# openSX70_ALADDIN_V399SEEED_20180220.net
KiCad netlist of a schematic drawn in EAGLE
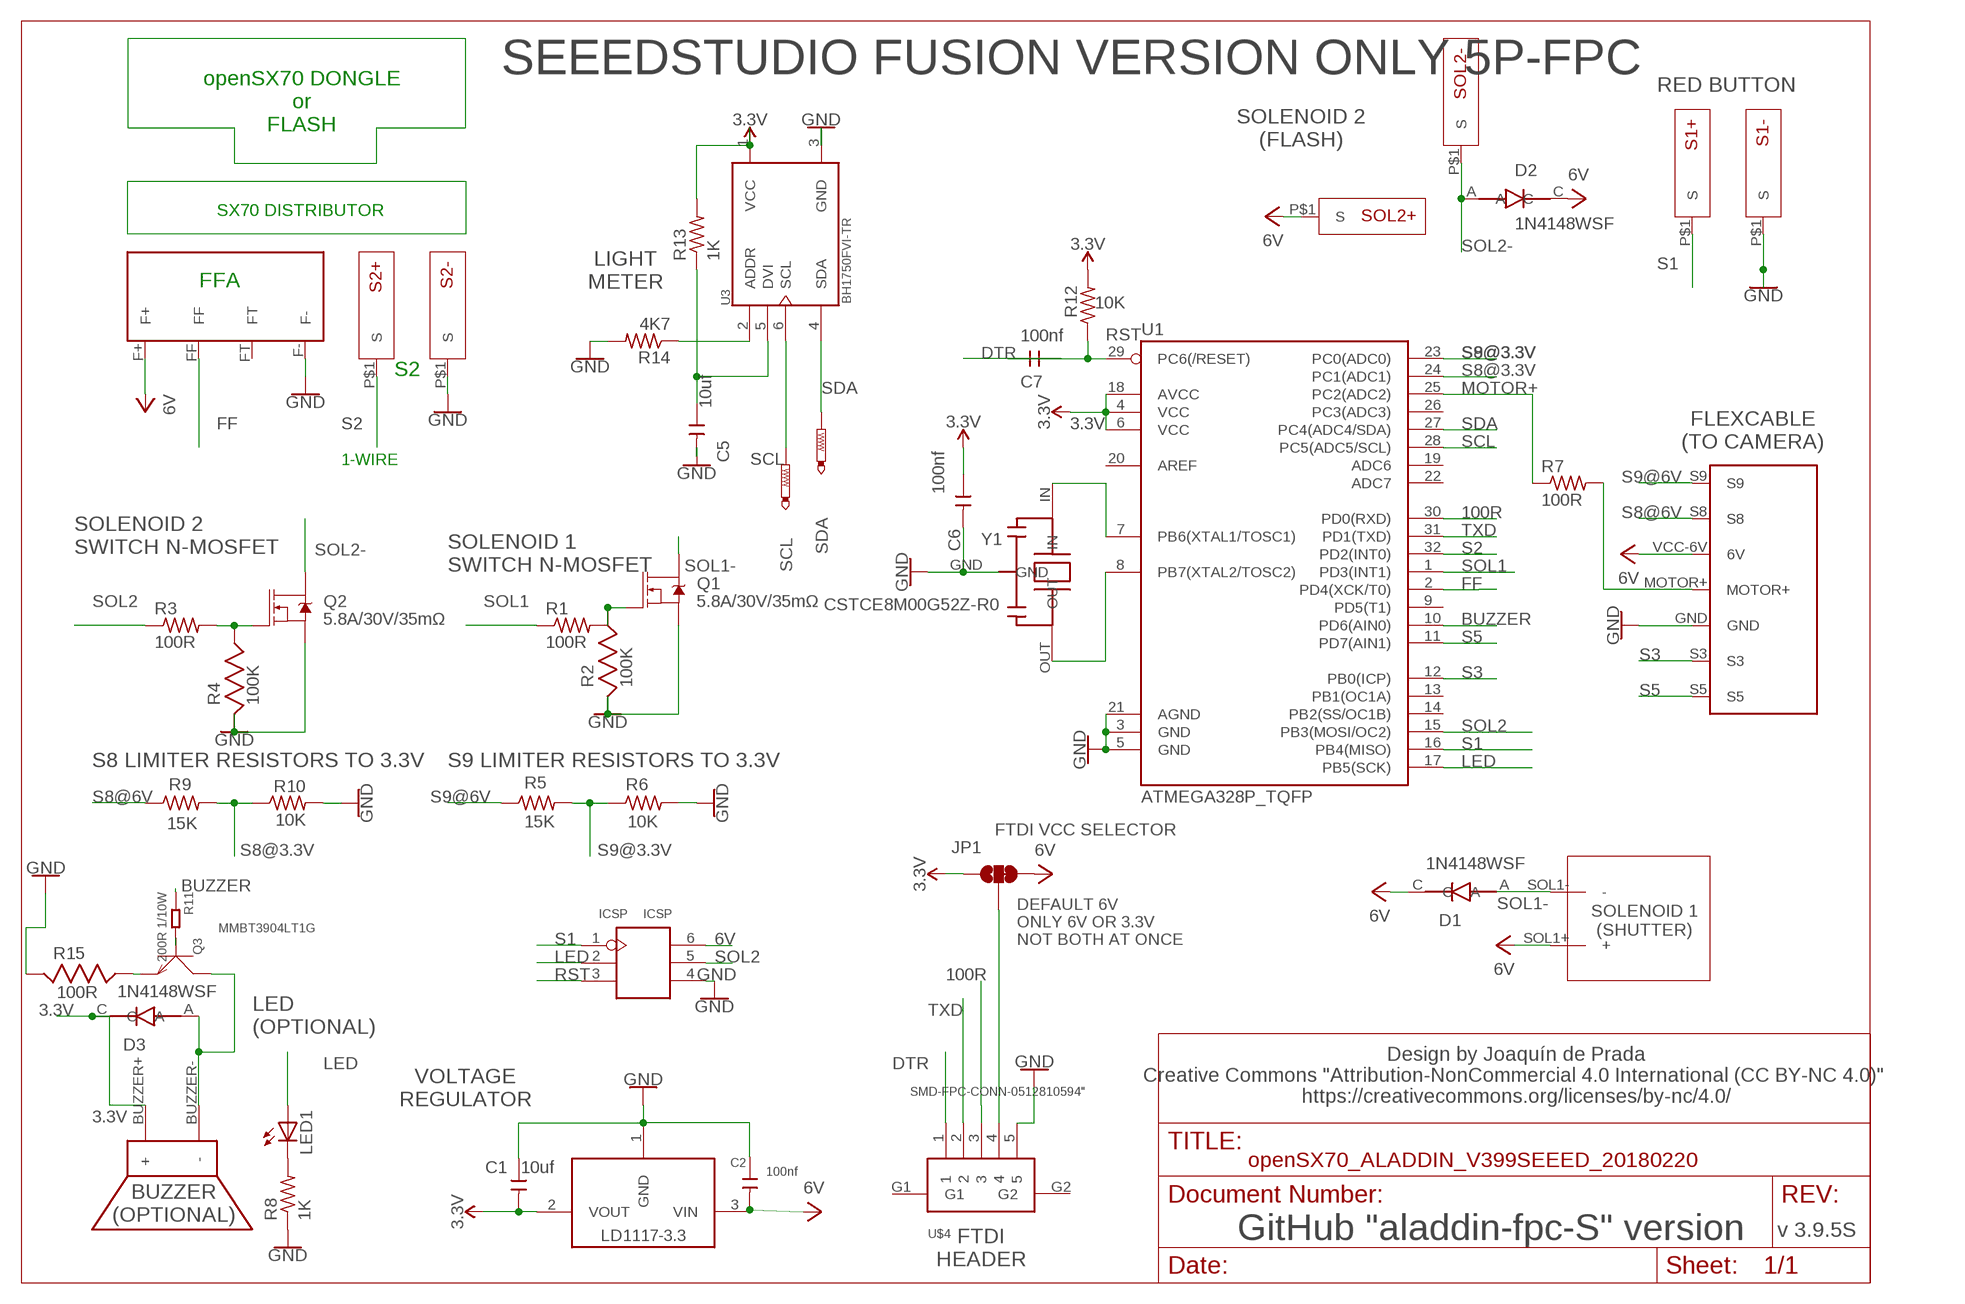
[diagram p0: schematic, sheet 1]

(export (version "E")
  (design (tool "Eeschema 10.0.6"))
  (components
    (comp (ref "C1")
      (value "10uf")
      (footprint "eagle-import:C0603")
      (fields (field (name "MPN") "CC0603KRX5R6BB106"))
      (libsource (lib "eagle-import") (part "CERAMIC-10UF-10V-10%-X5R(0603)"))
    )
    (comp (ref "C2")
      (value "100nf")
      (footprint "eagle-import:C0603")
      (fields (field (name "MPN") "CC0603KRX7R9BB104"))
      (libsource (lib "eagle-import") (part "CERAMIC-100NF-50V-10%-X7R(0603)"))
    )
    (comp (ref "C5")
      (value "10uf")
      (footprint "eagle-import:C0603")
      (fields (field (name "MPN") "CC0603KRX5R6BB106"))
      (libsource (lib "eagle-import") (part "CERAMIC-10UF-10V-10%-X5R(0603)"))
    )
    (comp (ref "C6")
      (value "100nf")
      (footprint "eagle-import:C0603")
      (fields (field (name "MPN") "CC0603KRX7R9BB104"))
      (libsource (lib "eagle-import") (part "CERAMIC-100NF-50V-10%-X7R(0603)"))
    )
    (comp (ref "C7")
      (value "100nf")
      (footprint "eagle-import:C0603")
      (fields (field (name "MPN") "CC0603KRX7R9BB104"))
      (libsource (lib "eagle-import") (part "CERAMIC-100NF-50V-10%-X7R(0603)"))
    )
    (comp (ref "D1")
      (value "1N4148WSF")
      (footprint "eagle-import:SODFL2512X100N")
      (fields (field (name "MANUFACTURER") "Fairchild Semiconductor"))
      (libsource (lib "eagle-import") (part "1N4148WS"))
    )
    (comp (ref "D2")
      (value "1N4148WSF")
      (footprint "eagle-import:SODFL2512X100N")
      (fields (field (name "MANUFACTURER") "Fairchild Semiconductor"))
      (libsource (lib "eagle-import") (part "1N4148WS"))
    )
    (comp (ref "D3")
      (value "1N4148WSF")
      (footprint "eagle-import:SODFL2512X100N")
      (fields (field (name "MANUFACTURER") "Fairchild Semiconductor"))
      (libsource (lib "eagle-import") (part "1N4148WS"))
    )
    (comp (ref "ICSP")
      (value "ICSP")
      (footprint "eagle-import:H2X3-2.54")
      (libsource (lib "eagle-import") (part "ICSP"))
    )
    (comp (ref "JP1")
      (value "FTDI VCC SELECTOR")
      (footprint "eagle-import:SMT-JUMPER_3_1-NC_TRACE_SILK")
      (libsource (lib "eagle-import") (part "JUMPER-SMT_3_1-NC_TRACE_SILK"))
    )
    (comp (ref "LD11172.5V")
      (value "LD1117 2.5V")
      (footprint "eagle-import:SOT223")
      (fields (field (name "MF") "Advanced Monolithic Systems") (field (name "MP") "AMS1117-5.0"))
      (libsource (lib "eagle-import") (part "LD1117-3.3"))
    )
    (comp (ref "LED1")
      (value "LEDCHIPLED_0805")
      (footprint "eagle-import:CHIPLED_0805")
      (libsource (lib "eagle-import") (part "LEDCHIPLED_0805"))
    )
    (comp (ref "Q1")
      (value "5.8A/30V/35mΩ")
      (footprint "eagle-import:SOT23-3")
      (libsource (lib "eagle-import") (part "MOSFET-NCH-AO3404A"))
    )
    (comp (ref "Q2")
      (value "5.8A/30V/35mΩ")
      (footprint "eagle-import:SOT23-3")
      (libsource (lib "eagle-import") (part "MOSFET-NCH-AO3404A"))
    )
    (comp (ref "Q3")
      (value "MMBT3904LT1G")
      (footprint "eagle-import:SOT-23")
      (libsource (lib "eagle-import") (part "SMD-TRANSISTORS-NPN-40V-200MA-MMBT3904LT1G(SOT-23)"))
    )
    (comp (ref "R1")
      (value "100R")
      (footprint "eagle-import:R0603")
      (libsource (lib "eagle-import") (part "R-US_R0603"))
    )
    (comp (ref "R2")
      (value "100K")
      (footprint "eagle-import:ERJ-3EKF1003V_RESC1608X55")
      (fields (field (name "MANUFACTURER") "PANASONIC"))
      (libsource (lib "eagle-import") (part "ERJ-3EKF1003V"))
    )
    (comp (ref "R3")
      (value "100R")
      (footprint "eagle-import:R0603")
      (libsource (lib "eagle-import") (part "R-US_R0603"))
    )
    (comp (ref "R4")
      (value "100K")
      (footprint "eagle-import:ERJ-3EKF1003V_RESC1608X55")
      (fields (field (name "MANUFACTURER") "PANASONIC"))
      (libsource (lib "eagle-import") (part "ERJ-3EKF1003V"))
    )
    (comp (ref "R5")
      (value "15K")
      (footprint "eagle-import:R0603")
      (libsource (lib "eagle-import") (part "R-US_R0603"))
    )
    (comp (ref "R6")
      (value "10K")
      (footprint "eagle-import:R0603")
      (libsource (lib "eagle-import") (part "R-US_R0603"))
    )
    (comp (ref "R7")
      (value "100R")
      (footprint "eagle-import:R0603")
      (libsource (lib "eagle-import") (part "R-US_R0603"))
    )
    (comp (ref "R8")
      (value "1K")
      (footprint "eagle-import:R0603")
      (libsource (lib "eagle-import") (part "R-US_R0603"))
    )
    (comp (ref "R9")
      (value "15K")
      (footprint "eagle-import:R0603")
      (libsource (lib "eagle-import") (part "R-US_R0603"))
    )
    (comp (ref "R10")
      (value "10K")
      (footprint "eagle-import:R0603")
      (libsource (lib "eagle-import") (part "R-US_R0603"))
    )
    (comp (ref "R11")
      (value "200R 1/10W")
      (footprint "eagle-import:R0603")
      (fields (field (name "MPN") "RC0603JR-07200RL"))
      (libsource (lib "eagle-import") (part "SMD-RES-200R-5%-1/10W(0603)"))
    )
    (comp (ref "R12")
      (value "10K")
      (footprint "eagle-import:R0603")
      (libsource (lib "eagle-import") (part "R-US_R0603"))
    )
    (comp (ref "R13")
      (value "1K")
      (footprint "eagle-import:R0603")
      (libsource (lib "eagle-import") (part "R-US_R0603"))
    )
    (comp (ref "R14")
      (value "4K7")
      (footprint "eagle-import:R0603")
      (libsource (lib "eagle-import") (part "R-US_R0603"))
    )
    (comp (ref "R15")
      (value "CRCW0603100RFKEA")
      (footprint "eagle-import:CRCW0603100RFKEA_RESC1608X55")
      (fields (field (name "MANUFACTURER") "VISHAY"))
      (libsource (lib "eagle-import") (part "CRCW0603100RFKEA"))
    )
    (comp (ref "S1+")
      (value "SX70-S-PAD-NEW")
      (footprint "eagle-import:SX70-S-PAD2")
      (libsource (lib "eagle-import") (part "SX70-S-PAD-NEW"))
    )
    (comp (ref "S1-")
      (value "SX70-S-PAD-NEW")
      (footprint "eagle-import:SX70-S-PAD2")
      (libsource (lib "eagle-import") (part "SX70-S-PAD-NEW"))
    )
    (comp (ref "S2+")
      (value "SX70-S-PAD-NEW")
      (footprint "eagle-import:SX70-S-PAD2")
      (libsource (lib "eagle-import") (part "SX70-S-PAD-NEW"))
    )
    (comp (ref "S2-")
      (value "SX70-S-PAD-NEW")
      (footprint "eagle-import:SX70-S-PAD2")
      (libsource (lib "eagle-import") (part "SX70-S-PAD-NEW"))
    )
    (comp (ref "SCL")
      (value "PTR1TP08R")
      (footprint "eagle-import:TP08R")
      (libsource (lib "eagle-import") (part "PTR1TP08R"))
    )
    (comp (ref "SDA")
      (value "PTR1TP08R")
      (footprint "eagle-import:TP08R")
      (libsource (lib "eagle-import") (part "PTR1TP08R"))
    )
    (comp (ref "SOL1")
      (value "SX70-SOLENOID1-2PADS")
      (footprint "eagle-import:SX70-SOLENOID1-2")
      (libsource (lib "eagle-import") (part "SX70-SOLENOID1-2PADS"))
    )
    (comp (ref "SOL2+")
      (value "SX70-S-PAD-NEW")
      (footprint "eagle-import:SX70-S-PAD2")
      (libsource (lib "eagle-import") (part "SX70-S-PAD-NEW"))
    )
    (comp (ref "SOL2-")
      (value "SX70-S-PAD-NEW")
      (footprint "eagle-import:SX70-S-PAD2")
      (libsource (lib "eagle-import") (part "SX70-S-PAD-NEW"))
    )
    (comp (ref "U$1")
      (value "SX70-7-PAD")
      (footprint "eagle-import:SX70-7-PAD")
      (libsource (lib "eagle-import") (part "SX70-7-PAD"))
    )
    (comp (ref "U$2")
      (value "FFA")
      (footprint "eagle-import:FFA-PAD-PACKAGE")
      (libsource (lib "eagle-import") (part "SX70-FFA-PAD"))
    )
    (comp (ref "U$3")
      (value "CSET8-5G_V2")
      (footprint "eagle-import:CSET8-5G_PACKAGE")
      (libsource (lib "eagle-import") (part "CSET8-5G_V2"))
    )
    (comp (ref "U$4")
      (value "SMD-FPC-CONN-0512810594\"")
      (footprint "eagle-import:51281-0594")
      (libsource (lib "eagle-import") (part "SMD-FPC-CONN-0512810594{dblquote}"))
    )
    (comp (ref "U1")
      (value "ATMEGA328P_TQFP")
      (footprint "eagle-import:TQFP32-08")
      (libsource (lib "eagle-import") (part "ATMEGA328P_TQFP"))
    )
    (comp (ref "U3")
      (value "BH1750FVI-TR")
      (footprint "eagle-import:SOTFL50P300X75-6N")
      (fields (field (name "MF") "Rohm"))
      (libsource (lib "eagle-import") (part "BH1750FVI-TR"))
    )
    (comp (ref "Y1")
      (value "CSTCE8M00G52Z-R0")
      (footprint "eagle-import:CFP95P160X100-3N")
      (fields (field (name "MF") "Murata") (field (name "MP") "CSTCE16M0V53-R0"))
      (libsource (lib "eagle-import") (part "CSTCE16M0V53-R0"))
    )
  )
  (nets
    (net (code "1") (name "/100R") (class "Default")
      (node (ref "U$4") (pin "3") (pinfunction "3_3") (pintype "bidirectional"))
      (node (ref "U1") (pin "30") (pinfunction "PD0(RXD)_30") (pintype "bidirectional"))
    )
    (net (code "2") (name "/BUZZER") (class "Default")
      (node (ref "R11") (pin "1") (pinfunction "1_1") (pintype "passive"))
      (node (ref "U1") (pin "10") (pinfunction "PD6(AIN0)_10") (pintype "bidirectional"))
    )
    (net (code "3") (name "/DTR") (class "Default")
      (node (ref "C7") (pin "1") (pinfunction "1_1") (pintype "passive"))
      (node (ref "U$4") (pin "1") (pinfunction "1_1") (pintype "bidirectional"))
    )
    (net (code "4") (name "/FF") (class "Default")
      (node (ref "U$2") (pin "FF") (pinfunction "FF_FF") (pintype "bidirectional"))
      (node (ref "U1") (pin "2") (pinfunction "PD4(XCK/T0)_2") (pintype "bidirectional"))
    )
    (net (code "5") (name "/LED") (class "Default")
      (node (ref "ICSP") (pin "2") (pinfunction "SCK_2") (pintype "bidirectional"))
      (node (ref "LED1") (pin "A") (pinfunction "A_A") (pintype "passive"))
      (node (ref "U1") (pin "17") (pinfunction "PB5(SCK)_17") (pintype "bidirectional"))
    )
    (net (code "6") (name "/MOTOR+") (class "Default")
      (node (ref "R7") (pin "1") (pinfunction "1_1") (pintype "passive"))
      (node (ref "U1") (pin "25") (pinfunction "PC2(ADC2)_25") (pintype "bidirectional"))
    )
    (net (code "7") (name "/RST") (class "Default")
      (node (ref "C7") (pin "2") (pinfunction "2_2") (pintype "passive"))
      (node (ref "ICSP") (pin "3") (pinfunction "RST_3") (pintype "bidirectional"))
      (node (ref "R12") (pin "1") (pinfunction "1_1") (pintype "passive"))
      (node (ref "U1") (pin "29") (pinfunction "PC6(/RESET)_29") (pintype "bidirectional"))
    )
    (net (code "8") (name "/S1") (class "Default")
      (node (ref "ICSP") (pin "1") (pinfunction "MISO_1") (pintype "bidirectional"))
      (node (ref "S1+") (pin "P$1") (pinfunction "S_P$1") (pintype "bidirectional"))
      (node (ref "U1") (pin "16") (pinfunction "PB4(MISO)_16") (pintype "bidirectional"))
    )
    (net (code "9") (name "/S2") (class "Default")
      (node (ref "S2+") (pin "P$1") (pinfunction "S_P$1") (pintype "bidirectional"))
      (node (ref "U1") (pin "32") (pinfunction "PD2(INT0)_32") (pintype "bidirectional"))
    )
    (net (code "10") (name "/S3") (class "Default")
      (node (ref "U$1") (pin "S3") (pinfunction "S3_S3") (pintype "bidirectional"))
      (node (ref "U1") (pin "12") (pinfunction "PB0(ICP)_12") (pintype "bidirectional"))
    )
    (net (code "11") (name "/S5") (class "Default")
      (node (ref "U$1") (pin "S5") (pinfunction "S5_S5") (pintype "bidirectional"))
      (node (ref "U1") (pin "11") (pinfunction "PD7(AIN1)_11") (pintype "bidirectional"))
    )
    (net (code "12") (name "/S8@3.3V") (class "Default")
      (node (ref "R10") (pin "1") (pinfunction "1_1") (pintype "passive"))
      (node (ref "R9") (pin "2") (pinfunction "2_2") (pintype "passive"))
      (node (ref "U1") (pin "24") (pinfunction "PC1(ADC1)_24") (pintype "bidirectional"))
    )
    (net (code "13") (name "/S8@6V") (class "Default")
      (node (ref "R9") (pin "1") (pinfunction "1_1") (pintype "passive"))
      (node (ref "U$1") (pin "S8") (pinfunction "S8_S8") (pintype "bidirectional"))
    )
    (net (code "14") (name "/S9@3.3V") (class "Default")
      (node (ref "R5") (pin "2") (pinfunction "2_2") (pintype "passive"))
      (node (ref "R6") (pin "1") (pinfunction "1_1") (pintype "passive"))
      (node (ref "U1") (pin "23") (pinfunction "PC0(ADC0)_23") (pintype "bidirectional"))
    )
    (net (code "15") (name "/S9@6V") (class "Default")
      (node (ref "R5") (pin "1") (pinfunction "1_1") (pintype "passive"))
      (node (ref "U$1") (pin "S9") (pinfunction "S9_S9") (pintype "bidirectional"))
    )
    (net (code "16") (name "/SCL") (class "Default")
      (node (ref "SCL") (pin "TP") (pinfunction "TP_TP") (pintype "input"))
      (node (ref "U1") (pin "28") (pinfunction "PC5(ADC5/SCL)_28") (pintype "bidirectional"))
      (node (ref "U3") (pin "6") (pinfunction "SCL_6") (pintype "input"))
    )
    (net (code "17") (name "/SDA") (class "Default")
      (node (ref "SDA") (pin "TP") (pinfunction "TP_TP") (pintype "input"))
      (node (ref "U1") (pin "27") (pinfunction "PC4(ADC4/SDA)_27") (pintype "bidirectional"))
      (node (ref "U3") (pin "4") (pinfunction "SDA_4") (pintype "bidirectional"))
    )
    (net (code "18") (name "/SOL1") (class "Default")
      (node (ref "R1") (pin "1") (pinfunction "1_1") (pintype "passive"))
      (node (ref "U1") (pin "1") (pinfunction "PD3(INT1)_1") (pintype "bidirectional"))
    )
    (net (code "19") (name "/SOL1-") (class "Default")
      (node (ref "D1") (pin "A") (pinfunction "A_A") (pintype "passive"))
      (node (ref "Q1") (pin "3") (pinfunction "D_3") (pintype "bidirectional"))
      (node (ref "SOL1") (pin "SOL1-") (pinfunction "-_SOL1-") (pintype "bidirectional"))
    )
    (net (code "20") (name "/SOL2") (class "Default")
      (node (ref "ICSP") (pin "5") (pinfunction "MOSI_5") (pintype "bidirectional"))
      (node (ref "R3") (pin "1") (pinfunction "1_1") (pintype "passive"))
      (node (ref "U1") (pin "15") (pinfunction "PB3(MOSI/OC2)_15") (pintype "bidirectional"))
    )
    (net (code "21") (name "/SOL2-") (class "Default")
      (node (ref "D2") (pin "A") (pinfunction "A_A") (pintype "passive"))
      (node (ref "Q2") (pin "3") (pinfunction "D_3") (pintype "bidirectional"))
      (node (ref "SOL2-") (pin "P$1") (pinfunction "S_P$1") (pintype "bidirectional"))
    )
    (net (code "22") (name "/TXD") (class "Default")
      (node (ref "U$4") (pin "2") (pinfunction "2_2") (pintype "bidirectional"))
      (node (ref "U1") (pin "31") (pinfunction "PD1(TXD)_31") (pintype "bidirectional"))
    )
    (net (code "23") (name "3.3V") (class "Default")
      (node (ref "C1") (pin "2") (pinfunction "2_2") (pintype "passive"))
      (node (ref "C6") (pin "1") (pinfunction "1_1") (pintype "passive"))
      (node (ref "D3") (pin "C") (pinfunction "C_C") (pintype "passive"))
      (node (ref "JP1") (pin "1") (pinfunction "1_1") (pintype "passive"))
      (node (ref "LD11172.5V") (pin "2") (pinfunction "VOUT_2") (pintype "bidirectional"))
      (node (ref "R12") (pin "2") (pinfunction "2_2") (pintype "passive"))
      (node (ref "R13") (pin "2") (pinfunction "2_2") (pintype "passive"))
      (node (ref "U$3") (pin "BUZZER+") (pinfunction "+_BUZZER+") (pintype "bidirectional"))
      (node (ref "U1") (pin "18") (pinfunction "AVCC_18") (pintype "bidirectional"))
      (node (ref "U1") (pin "4") (pinfunction "VCC_4") (pintype "bidirectional"))
      (node (ref "U1") (pin "6") (pinfunction "VCC_6") (pintype "bidirectional"))
      (node (ref "U3") (pin "1") (pinfunction "VCC_1") (pintype "power_in"))
    )
    (net (code "24") (name "6V") (class "Default")
      (node (ref "C2") (pin "2") (pinfunction "2_2") (pintype "passive"))
      (node (ref "D1") (pin "C") (pinfunction "C_C") (pintype "passive"))
      (node (ref "D2") (pin "C") (pinfunction "C_C") (pintype "passive"))
      (node (ref "ICSP") (pin "6") (pinfunction "VCC_6") (pintype "bidirectional"))
      (node (ref "JP1") (pin "3") (pinfunction "3_3") (pintype "passive"))
      (node (ref "LD11172.5V") (pin "3") (pinfunction "VIN_3") (pintype "bidirectional"))
      (node (ref "SOL1") (pin "SOL1+") (pinfunction "+_SOL1+") (pintype "bidirectional"))
      (node (ref "SOL2+") (pin "P$1") (pinfunction "S_P$1") (pintype "bidirectional"))
      (node (ref "U$1") (pin "VCC-6V") (pinfunction "6V_VCC-6V") (pintype "bidirectional"))
      (node (ref "U$2") (pin "F+") (pinfunction "F+_F+") (pintype "bidirectional"))
    )
    (net (code "25") (name "GND") (class "Default")
      (node (ref "C1") (pin "1") (pinfunction "1_1") (pintype "passive"))
      (node (ref "C2") (pin "1") (pinfunction "1_1") (pintype "passive"))
      (node (ref "C5") (pin "2") (pinfunction "2_2") (pintype "passive"))
      (node (ref "C6") (pin "2") (pinfunction "2_2") (pintype "passive"))
      (node (ref "ICSP") (pin "4") (pinfunction "GND_4") (pintype "bidirectional"))
      (node (ref "LD11172.5V") (pin "1") (pinfunction "GND_1") (pintype "bidirectional"))
      (node (ref "Q1") (pin "2") (pinfunction "S_2") (pintype "bidirectional"))
      (node (ref "Q2") (pin "2") (pinfunction "S_2") (pintype "bidirectional"))
      (node (ref "R10") (pin "2") (pinfunction "2_2") (pintype "passive"))
      (node (ref "R14") (pin "2") (pinfunction "2_2") (pintype "passive"))
      (node (ref "R15") (pin "1") (pinfunction "1_1") (pintype "passive"))
      (node (ref "R2") (pin "1") (pinfunction "1_1") (pintype "passive"))
      (node (ref "R4") (pin "1") (pinfunction "1_1") (pintype "passive"))
      (node (ref "R6") (pin "2") (pinfunction "2_2") (pintype "passive"))
      (node (ref "R8") (pin "1") (pinfunction "1_1") (pintype "passive"))
      (node (ref "S1-") (pin "P$1") (pinfunction "S_P$1") (pintype "bidirectional"))
      (node (ref "S2-") (pin "P$1") (pinfunction "S_P$1") (pintype "bidirectional"))
      (node (ref "U$1") (pin "GND") (pinfunction "GND_GND") (pintype "bidirectional"))
      (node (ref "U$2") (pin "F-") (pinfunction "F-_F-") (pintype "bidirectional"))
      (node (ref "U$4") (pin "5") (pinfunction "5_5") (pintype "bidirectional"))
      (node (ref "U1") (pin "21") (pinfunction "AGND_21") (pintype "bidirectional"))
      (node (ref "U1") (pin "3") (pinfunction "GND_3") (pintype "bidirectional"))
      (node (ref "U1") (pin "5") (pinfunction "GND_5") (pintype "bidirectional"))
      (node (ref "U3") (pin "3") (pinfunction "GND_3") (pintype "power_in"))
      (node (ref "Y1") (pin "GND") (pinfunction "GND_GND") (pintype "passive"))
    )
    (net (code "26") (name "Net-(JP1-Pad2)") (class "Default")
      (node (ref "JP1") (pin "2") (pinfunction "2_2") (pintype "passive"))
      (node (ref "U$4") (pin "4") (pinfunction "4_4") (pintype "bidirectional"))
    )
    (net (code "27") (name "Net-(LED1-PadC)") (class "Default")
      (node (ref "LED1") (pin "C") (pinfunction "C_C") (pintype "passive"))
      (node (ref "R8") (pin "2") (pinfunction "2_2") (pintype "passive"))
    )
    (net (code "28") (name "Net-(Q1-G)") (class "Default")
      (node (ref "Q1") (pin "1") (pinfunction "G_1") (pintype "bidirectional"))
      (node (ref "R1") (pin "2") (pinfunction "2_2") (pintype "passive"))
      (node (ref "R2") (pin "2") (pinfunction "2_2") (pintype "passive"))
    )
    (net (code "29") (name "Net-(Q2-G)") (class "Default")
      (node (ref "Q2") (pin "1") (pinfunction "G_1") (pintype "bidirectional"))
      (node (ref "R3") (pin "2") (pinfunction "2_2") (pintype "passive"))
      (node (ref "R4") (pin "2") (pinfunction "2_2") (pintype "passive"))
    )
    (net (code "30") (name "Net-(Q3-B)") (class "Default")
      (node (ref "Q3") (pin "1") (pinfunction "B_1") (pintype "passive"))
      (node (ref "R11") (pin "2") (pinfunction "2_2") (pintype "passive"))
    )
    (net (code "31") (name "Net-(Q3-C)") (class "Default")
      (node (ref "D3") (pin "A") (pinfunction "A_A") (pintype "passive"))
      (node (ref "Q3") (pin "3") (pinfunction "C_3") (pintype "passive"))
      (node (ref "U$3") (pin "BUZZER-") (pinfunction "-_BUZZER-") (pintype "bidirectional"))
    )
    (net (code "32") (name "Net-(Q3-E)") (class "Default")
      (node (ref "Q3") (pin "2") (pinfunction "E_2") (pintype "passive"))
      (node (ref "R15") (pin "2") (pinfunction "2_2") (pintype "passive"))
    )
    (net (code "33") (name "Net-(R7-Pad2)") (class "Default")
      (node (ref "R7") (pin "2") (pinfunction "2_2") (pintype "passive"))
      (node (ref "U$1") (pin "MOTOR+") (pinfunction "MOTOR+_MOTOR+") (pintype "bidirectional"))
    )
    (net (code "34") (name "Net-(U1-PB6(XTAL1{slash}TOSC1))") (class "Default")
      (node (ref "U1") (pin "7") (pinfunction "PB6(XTAL1/TOSC1)_7") (pintype "bidirectional"))
      (node (ref "Y1") (pin "IN") (pinfunction "IN_IN") (pintype "input"))
    )
    (net (code "35") (name "Net-(U1-PB7(XTAL2{slash}TOSC2))") (class "Default")
      (node (ref "U1") (pin "8") (pinfunction "PB7(XTAL2/TOSC2)_8") (pintype "bidirectional"))
      (node (ref "Y1") (pin "OUT") (pinfunction "OUT_OUT") (pintype "output"))
    )
    (net (code "36") (name "Net-(U3-ADDR)") (class "Default")
      (node (ref "R14") (pin "1") (pinfunction "1_1") (pintype "passive"))
      (node (ref "U3") (pin "2") (pinfunction "ADDR_2") (pintype "input"))
    )
    (net (code "37") (name "Net-(U3-DVI)") (class "Default")
      (node (ref "C5") (pin "1") (pinfunction "1_1") (pintype "passive"))
      (node (ref "R13") (pin "1") (pinfunction "1_1") (pintype "passive"))
      (node (ref "U3") (pin "5") (pinfunction "DVI_5") (pintype "input"))
    )
    (net (code "38") (name "unconnected-(U$2-PadFT)") (class "Default")
      (node (ref "U$2") (pin "FT") (pinfunction "FT_FT") (pintype "bidirectional"))
    )
    (net (code "39") (name "unconnected-(U$4-PadG1)") (class "Default")
      (node (ref "U$4") (pin "G1") (pinfunction "G1_G1") (pintype "bidirectional"))
    )
    (net (code "40") (name "unconnected-(U$4-PadG2)") (class "Default")
      (node (ref "U$4") (pin "G2") (pinfunction "G2_G2") (pintype "bidirectional"))
    )
    (net (code "41") (name "unconnected-(U1-ADC6-Pad19)") (class "Default")
      (node (ref "U1") (pin "19") (pinfunction "ADC6_19") (pintype "bidirectional"))
    )
    (net (code "42") (name "unconnected-(U1-ADC7-Pad22)") (class "Default")
      (node (ref "U1") (pin "22") (pinfunction "ADC7_22") (pintype "bidirectional"))
    )
    (net (code "43") (name "unconnected-(U1-AREF-Pad20)") (class "Default")
      (node (ref "U1") (pin "20") (pinfunction "AREF_20") (pintype "bidirectional"))
    )
    (net (code "44") (name "unconnected-(U1-PB1(OC1A)-Pad13)") (class "Default")
      (node (ref "U1") (pin "13") (pinfunction "PB1(OC1A)_13") (pintype "bidirectional"))
    )
    (net (code "45") (name "unconnected-(U1-PB2(SS{slash}OC1B)-Pad14)") (class "Default")
      (node (ref "U1") (pin "14") (pinfunction "PB2(SS/OC1B)_14") (pintype "bidirectional"))
    )
    (net (code "46") (name "unconnected-(U1-PC3(ADC3)-Pad26)") (class "Default")
      (node (ref "U1") (pin "26") (pinfunction "PC3(ADC3)_26") (pintype "bidirectional"))
    )
    (net (code "47") (name "unconnected-(U1-PD5(T1)-Pad9)") (class "Default")
      (node (ref "U1") (pin "9") (pinfunction "PD5(T1)_9") (pintype "bidirectional"))
    )
  )
)
